# LM1117_3_3V_Reg.net
KiCad netlist of a schematic drawn in Altium Designer
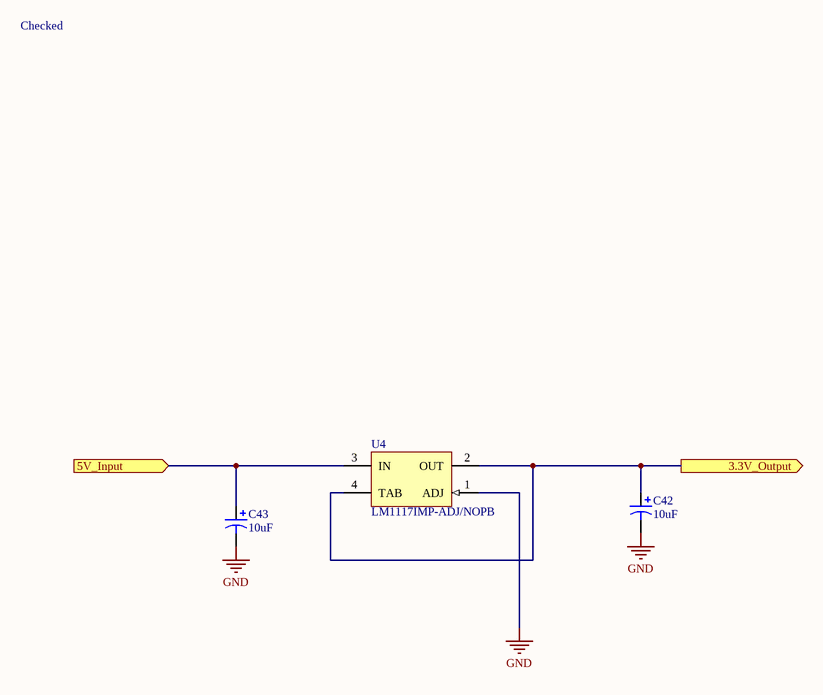
[diagram p0: LM1117_3.3V_Reg.SchDoc]

(export (version "E")
  (design (tool "Eeschema 10.0.6"))
  (components
    (comp (ref "C42")
      (value "10uF")
      (footprint "CAPACITOR_3MM")
      (description "CAP 85C 0.1uF ±20% 50V WX Series Aluminum Electrolytic")
      (fields (field (name "MPN") "UWX1H0R1MCL2GB") (field (name "Comment") "Pol"))
      (libsource (lib "esd_library") (part "Cap Polar-0.1uF-50V"))
    )
    (comp (ref "C43")
      (value "10uF")
      (footprint "CAPACITOR_3MM")
      (description "CAP 85C 0.1uF ±20% 50V WX Series Aluminum Electrolytic")
      (fields (field (name "MPN") "UWX1H0R1MCL2GB") (field (name "Comment") "Pol"))
      (libsource (lib "esd_library") (part "Cap Polar-0.1uF-50V"))
    )
    (comp (ref "U4")
      (value "LM1117IMP-ADJ/NOPB")
      (footprint "MP04A_L")
      (description "800mA Low-Dropout Linear Regulator, 4-pin SOT-223, Pb-Free")
      (fields
        (field (name "MANUFACTURER") "National Semiconductor")
        (field (name "MPN") "LM1117MP-3.3/NOPB")
        (field (name "PUBLISHER") "Altium Limited")
      )
      (libsource (lib "esd_library") (part "LM1117IMP-ADJ/NOPB"))
    )
  )
  (nets
    (net (code "1") (name "/3.3V_Output") (class "Default")
      (node (ref "C42") (pin "1") (pinfunction "1_1") (pintype "passive"))
      (node (ref "U4") (pin "2") (pinfunction "OUT_2") (pintype "power_in"))
      (node (ref "U4") (pin "4") (pinfunction "TAB_4") (pintype "power_in"))
    )
    (net (code "2") (name "/5V_Input") (class "Default")
      (node (ref "C43") (pin "1") (pinfunction "1_1") (pintype "passive"))
      (node (ref "U4") (pin "3") (pinfunction "IN_3") (pintype "power_in"))
    )
    (net (code "3") (name "GND") (class "Default")
      (node (ref "C42") (pin "2") (pinfunction "2_2") (pintype "passive"))
      (node (ref "C43") (pin "2") (pinfunction "2_2") (pintype "passive"))
      (node (ref "U4") (pin "1") (pinfunction "ADJ_1") (pintype "input"))
    )
  )
)
